# DVT-LPF.net
KiCad netlist of a schematic drawn in Altium Designer
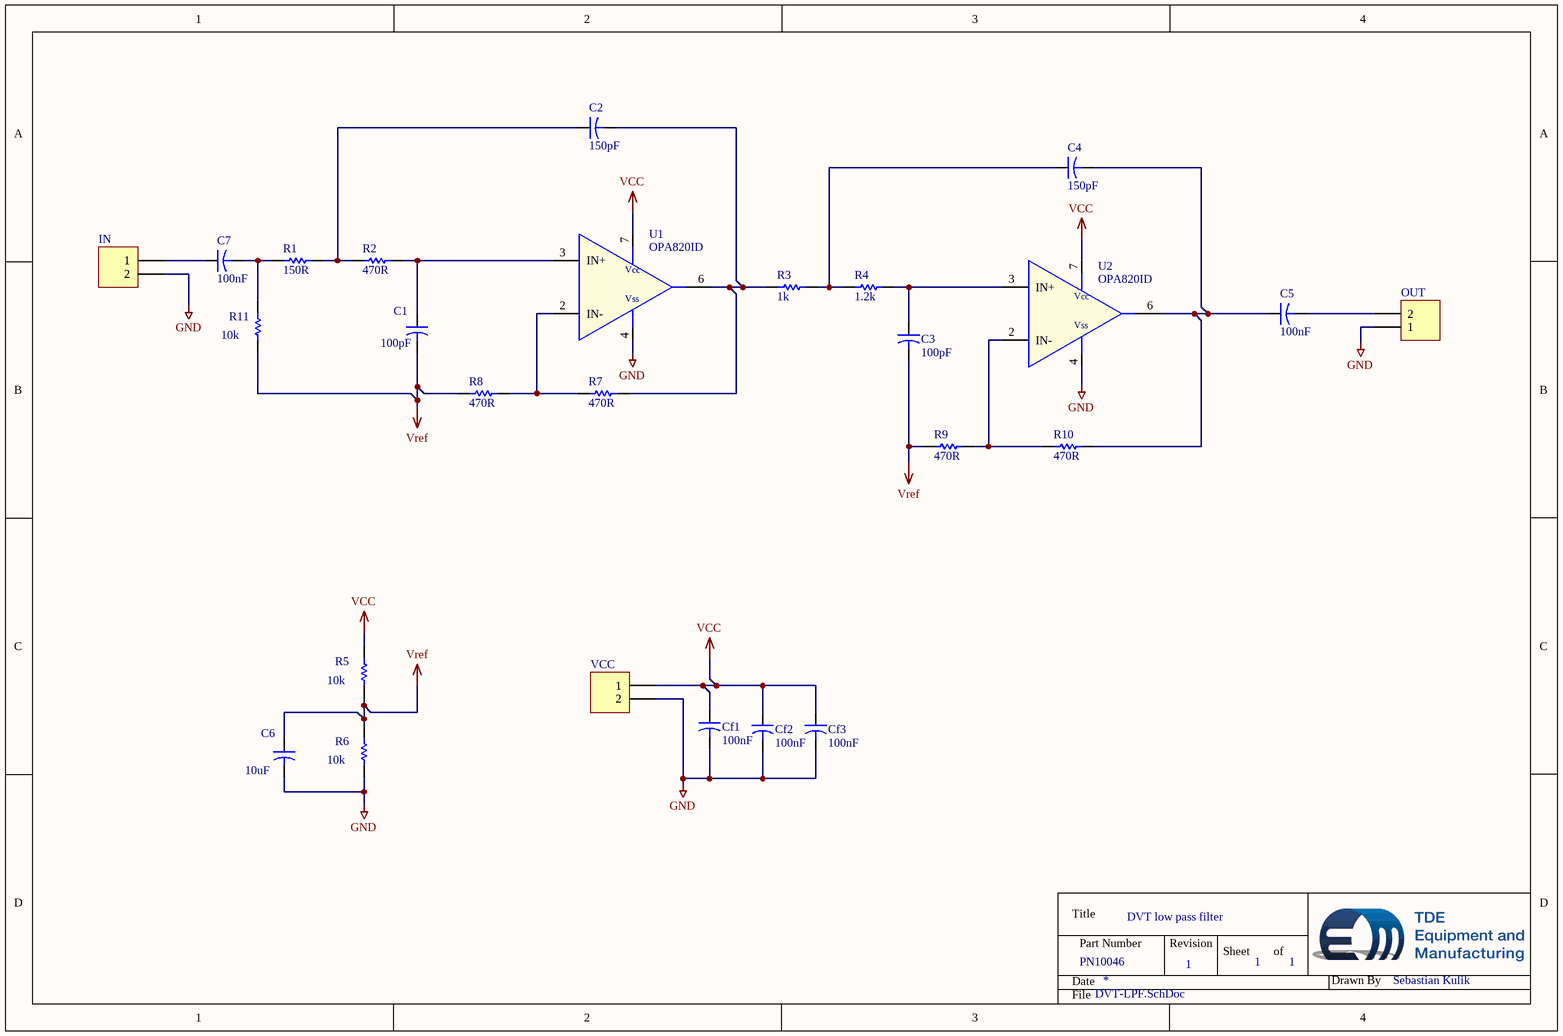
[diagram p0: DVT-LPF.SchDoc]

(export (version "E")
  (design (tool "Eeschema 10.0.6"))
  (components
    (comp (ref "*") (value "Om") (footprint "Om-5mm") (libsource (lib "ICs") (part "Om")))
    (comp (ref "-") (value "Om") (footprint "Om-5mm") (libsource (lib "ICs") (part "Om")))
    (comp (ref "C1")
      (value "100pF")
      (footprint "Dummy-10mm")
      (description "Capacitor-Dummy-THT")
      (fields (field (name "PUBLISHER") "Sebastian Kulik"))
      (libsource (lib "Capacitors") (part "Capacitor-Dummy-THT"))
    )
    (comp (ref "C2")
      (value "150pF")
      (footprint "Dummy-10mm")
      (description "Capacitor-Dummy-THT")
      (fields (field (name "PUBLISHER") "Sebastian Kulik"))
      (libsource (lib "Capacitors") (part "Capacitor-Dummy-THT"))
    )
    (comp (ref "C3")
      (value "100pF")
      (footprint "Dummy-10mm")
      (description "Capacitor-Dummy-THT")
      (fields (field (name "PUBLISHER") "Sebastian Kulik"))
      (libsource (lib "Capacitors") (part "Capacitor-Dummy-THT"))
    )
    (comp (ref "C4")
      (value "150pF")
      (footprint "Dummy-10mm")
      (description "Capacitor-Dummy-THT")
      (fields (field (name "PUBLISHER") "Sebastian Kulik"))
      (libsource (lib "Capacitors") (part "Capacitor-Dummy-THT"))
    )
    (comp (ref "C5")
      (value "100nF")
      (footprint "Dummy-10mm")
      (description "Capacitor-Dummy-THT")
      (fields (field (name "PUBLISHER") "Sebastian Kulik"))
      (libsource (lib "Capacitors") (part "Capacitor-Dummy-THT"))
    )
    (comp (ref "C6")
      (value "10uF")
      (footprint "Dummy-10mm")
      (description "Capacitor-Dummy-THT")
      (fields (field (name "PUBLISHER") "Sebastian Kulik"))
      (libsource (lib "Capacitors") (part "Capacitor-Dummy-THT"))
    )
    (comp (ref "C7")
      (value "100nF")
      (footprint "Dummy-10mm")
      (description "Capacitor-Dummy-THT")
      (fields (field (name "PUBLISHER") "Sebastian Kulik"))
      (libsource (lib "Capacitors") (part "Capacitor-Dummy-THT"))
    )
    (comp (ref "Cf1")
      (value "100nF")
      (footprint "Dummy-10mm")
      (description "Capacitor-Dummy-THT")
      (fields (field (name "PUBLISHER") "Sebastian Kulik"))
      (libsource (lib "Capacitors") (part "Capacitor-Dummy-THT"))
    )
    (comp (ref "Cf2")
      (value "100nF")
      (footprint "Dummy-10mm")
      (description "Capacitor-Dummy-THT")
      (fields (field (name "PUBLISHER") "Sebastian Kulik"))
      (libsource (lib "Capacitors") (part "Capacitor-Dummy-THT"))
    )
    (comp (ref "Cf3")
      (value "100nF")
      (footprint "Dummy-10mm")
      (description "Capacitor-Dummy-THT")
      (fields (field (name "PUBLISHER") "Sebastian Kulik"))
      (libsource (lib "Capacitors") (part "Capacitor-Dummy-THT"))
    )
    (comp (ref "IN")
      (value "PHOENIX_1715721")
      (footprint "Phoenix-2-5_08")
      (description "Phoenix, 2 pol, 5.08mm, 22A, 715721")
      (fields (field (name "MANUFACTURER") "Phoenix") (field (name "PUBLISHER") "Sebastian Kulik"))
      (libsource (lib "Connectors") (part "2Pol_1715721"))
    )
    (comp (ref "OUT")
      (value "PHOENIX_1715721")
      (footprint "Phoenix-2-5_08")
      (description "Phoenix, 2 pol, 5.08mm, 22A, 715721")
      (fields (field (name "MANUFACTURER") "Phoenix") (field (name "PUBLISHER") "Sebastian Kulik"))
      (libsource (lib "") (part "2Pol_1715721_1"))
    )
    (comp (ref "R1")
      (value "150R")
      (footprint "Dummy-10mm")
      (description "Resistor-Dummy-THT")
      (fields (field (name "PUBLISHER") "Sebastian Kulik"))
      (libsource (lib "Resistors") (part "Resistor-Dummy-THT"))
    )
    (comp (ref "R2")
      (value "470R")
      (footprint "Dummy-10mm")
      (description "Resistor-Dummy-THT")
      (fields (field (name "PUBLISHER") "Sebastian Kulik"))
      (libsource (lib "Resistors") (part "Resistor-Dummy-THT"))
    )
    (comp (ref "R3")
      (value "1k")
      (footprint "Dummy-10mm")
      (description "Resistor-Dummy-THT")
      (fields (field (name "PUBLISHER") "Sebastian Kulik"))
      (libsource (lib "Resistors") (part "Resistor-Dummy-THT"))
    )
    (comp (ref "R4")
      (value "1.2k")
      (footprint "Dummy-10mm")
      (description "Resistor-Dummy-THT")
      (fields (field (name "PUBLISHER") "Sebastian Kulik"))
      (libsource (lib "Resistors") (part "Resistor-Dummy-THT"))
    )
    (comp (ref "R5")
      (value "10k")
      (footprint "Dummy-10mm")
      (description "Resistor-Dummy-THT")
      (fields (field (name "PUBLISHER") "Sebastian Kulik"))
      (libsource (lib "Resistors") (part "Resistor-Dummy-THT"))
    )
    (comp (ref "R6")
      (value "10k")
      (footprint "Dummy-10mm")
      (description "Resistor-Dummy-THT")
      (fields (field (name "PUBLISHER") "Sebastian Kulik"))
      (libsource (lib "Resistors") (part "Resistor-Dummy-THT"))
    )
    (comp (ref "R7")
      (value "470R")
      (footprint "Dummy-10mm")
      (description "Resistor-Dummy-THT")
      (fields (field (name "PUBLISHER") "Sebastian Kulik"))
      (libsource (lib "Resistors") (part "Resistor-Dummy-THT"))
    )
    (comp (ref "R8")
      (value "470R")
      (footprint "Dummy-10mm")
      (description "Resistor-Dummy-THT")
      (fields (field (name "PUBLISHER") "Sebastian Kulik"))
      (libsource (lib "Resistors") (part "Resistor-Dummy-THT"))
    )
    (comp (ref "R9")
      (value "470R")
      (footprint "Dummy-10mm")
      (description "Resistor-Dummy-THT")
      (fields (field (name "PUBLISHER") "Sebastian Kulik"))
      (libsource (lib "Resistors") (part "Resistor-Dummy-THT"))
    )
    (comp (ref "R10")
      (value "470R")
      (footprint "Dummy-10mm")
      (description "Resistor-Dummy-THT")
      (fields (field (name "PUBLISHER") "Sebastian Kulik"))
      (libsource (lib "Resistors") (part "Resistor-Dummy-THT"))
    )
    (comp (ref "R11")
      (value "10k")
      (footprint "Dummy-10mm")
      (description "Resistor-Dummy-THT")
      (fields (field (name "PUBLISHER") "Sebastian Kulik"))
      (libsource (lib "Resistors") (part "Resistor-Dummy-THT"))
    )
    (comp (ref "U1")
      (value "OPA820ID")
      (footprint "SOP8_L")
      (description "High speed OP, 260MHz")
      (fields (field (name "MANUFACTURER") "TI") (field (name "PUBLISHER") "Sebastian Kulik"))
      (libsource (lib "ICs") (part "OPA820ID"))
    )
    (comp (ref "U2")
      (value "OPA820ID")
      (footprint "SOP8_L")
      (description "High speed OP, 260MHz")
      (fields (field (name "MANUFACTURER") "TI") (field (name "PUBLISHER") "Sebastian Kulik"))
      (libsource (lib "ICs") (part "OPA820ID"))
    )
    (comp (ref "VCC")
      (value "PHOENIX_1715721")
      (footprint "Phoenix-2-5_08")
      (description "Phoenix, 2 pol, 5.08mm, 22A, 715721")
      (fields (field (name "MANUFACTURER") "Phoenix") (field (name "PUBLISHER") "Sebastian Kulik"))
      (libsource (lib "Connectors") (part "2Pol_1715721"))
    )
  )
  (nets
    (net (code "1") (name "GND") (class "Default")
      (node (ref "C6") (pin "2") (pinfunction "2_2") (pintype "passive"))
      (node (ref "Cf1") (pin "2") (pinfunction "2_2") (pintype "passive"))
      (node (ref "Cf2") (pin "2") (pinfunction "2_2") (pintype "passive"))
      (node (ref "Cf3") (pin "2") (pinfunction "2_2") (pintype "passive"))
      (node (ref "IN") (pin "2") (pinfunction "2_2") (pintype "passive"))
      (node (ref "OUT") (pin "1") (pinfunction "1_1") (pintype "passive"))
      (node (ref "R6") (pin "1") (pinfunction "1_1") (pintype "passive"))
      (node (ref "U1") (pin "4") (pinfunction "Vss_4") (pintype "passive"))
      (node (ref "U2") (pin "4") (pinfunction "Vss_4") (pintype "passive"))
      (node (ref "VCC") (pin "2") (pinfunction "2_2") (pintype "passive"))
    )
    (net (code "2") (name "Net-(C2-Pad1)") (class "Default")
      (node (ref "C2") (pin "1") (pinfunction "1_1") (pintype "passive"))
      (node (ref "R1") (pin "1") (pinfunction "1_1") (pintype "passive"))
      (node (ref "R2") (pin "2") (pinfunction "2_2") (pintype "passive"))
    )
    (net (code "3") (name "Net-(C4-Pad1)") (class "Default")
      (node (ref "C4") (pin "1") (pinfunction "1_1") (pintype "passive"))
      (node (ref "R3") (pin "1") (pinfunction "1_1") (pintype "passive"))
      (node (ref "R4") (pin "2") (pinfunction "2_2") (pintype "passive"))
    )
    (net (code "4") (name "Net-(C5-Pad2)") (class "Default")
      (node (ref "C5") (pin "2") (pinfunction "2_2") (pintype "passive"))
      (node (ref "OUT") (pin "2") (pinfunction "2_2") (pintype "passive"))
    )
    (net (code "5") (name "Net-(C7-Pad1)") (class "Default")
      (node (ref "C7") (pin "1") (pinfunction "1_1") (pintype "passive"))
      (node (ref "IN") (pin "1") (pinfunction "1_1") (pintype "passive"))
    )
    (net (code "6") (name "Net-(C7-Pad2)") (class "Default")
      (node (ref "C7") (pin "2") (pinfunction "2_2") (pintype "passive"))
      (node (ref "R1") (pin "2") (pinfunction "2_2") (pintype "passive"))
      (node (ref "R11") (pin "2") (pinfunction "2_2") (pintype "passive"))
    )
    (net (code "7") (name "Net-(U1-IN+)") (class "Default")
      (node (ref "C1") (pin "1") (pinfunction "1_1") (pintype "passive"))
      (node (ref "R2") (pin "1") (pinfunction "1_1") (pintype "passive"))
      (node (ref "U1") (pin "3") (pinfunction "IN+_3") (pintype "power_in"))
    )
    (net (code "8") (name "Net-(U1-IN-)") (class "Default")
      (node (ref "R7") (pin "2") (pinfunction "2_2") (pintype "passive"))
      (node (ref "R8") (pin "1") (pinfunction "1_1") (pintype "passive"))
      (node (ref "U1") (pin "2") (pinfunction "IN-_2") (pintype "passive"))
    )
    (net (code "9") (name "Net-(U1-OUT)") (class "Default")
      (node (ref "C2") (pin "2") (pinfunction "2_2") (pintype "passive"))
      (node (ref "R3") (pin "2") (pinfunction "2_2") (pintype "passive"))
      (node (ref "R7") (pin "1") (pinfunction "1_1") (pintype "passive"))
      (node (ref "U1") (pin "6") (pinfunction "OUT_6") (pintype "passive"))
    )
    (net (code "10") (name "Net-(U2-IN+)") (class "Default")
      (node (ref "C3") (pin "1") (pinfunction "1_1") (pintype "passive"))
      (node (ref "R4") (pin "1") (pinfunction "1_1") (pintype "passive"))
      (node (ref "U2") (pin "3") (pinfunction "IN+_3") (pintype "power_in"))
    )
    (net (code "11") (name "Net-(U2-IN-)") (class "Default")
      (node (ref "R10") (pin "2") (pinfunction "2_2") (pintype "passive"))
      (node (ref "R9") (pin "1") (pinfunction "1_1") (pintype "passive"))
      (node (ref "U2") (pin "2") (pinfunction "IN-_2") (pintype "passive"))
    )
    (net (code "12") (name "Net-(U2-OUT)") (class "Default")
      (node (ref "C4") (pin "2") (pinfunction "2_2") (pintype "passive"))
      (node (ref "C5") (pin "1") (pinfunction "1_1") (pintype "passive"))
      (node (ref "R10") (pin "1") (pinfunction "1_1") (pintype "passive"))
      (node (ref "U2") (pin "6") (pinfunction "OUT_6") (pintype "passive"))
    )
    (net (code "13") (name "VCC") (class "Default")
      (node (ref "Cf1") (pin "1") (pinfunction "1_1") (pintype "passive"))
      (node (ref "Cf2") (pin "1") (pinfunction "1_1") (pintype "passive"))
      (node (ref "Cf3") (pin "1") (pinfunction "1_1") (pintype "passive"))
      (node (ref "R5") (pin "2") (pinfunction "2_2") (pintype "passive"))
      (node (ref "U1") (pin "7") (pinfunction "Vcc_7") (pintype "passive"))
      (node (ref "U2") (pin "7") (pinfunction "Vcc_7") (pintype "passive"))
      (node (ref "VCC") (pin "1") (pinfunction "1_1") (pintype "passive"))
    )
    (net (code "14") (name "Vref") (class "Default")
      (node (ref "C1") (pin "2") (pinfunction "2_2") (pintype "passive"))
      (node (ref "C3") (pin "2") (pinfunction "2_2") (pintype "passive"))
      (node (ref "C6") (pin "1") (pinfunction "1_1") (pintype "passive"))
      (node (ref "R11") (pin "1") (pinfunction "1_1") (pintype "passive"))
      (node (ref "R5") (pin "1") (pinfunction "1_1") (pintype "passive"))
      (node (ref "R6") (pin "2") (pinfunction "2_2") (pintype "passive"))
      (node (ref "R8") (pin "2") (pinfunction "2_2") (pintype "passive"))
      (node (ref "R9") (pin "2") (pinfunction "2_2") (pintype "passive"))
    )
  )
)
